# JTAG.net
KiCad netlist of a schematic drawn in Altium Designer
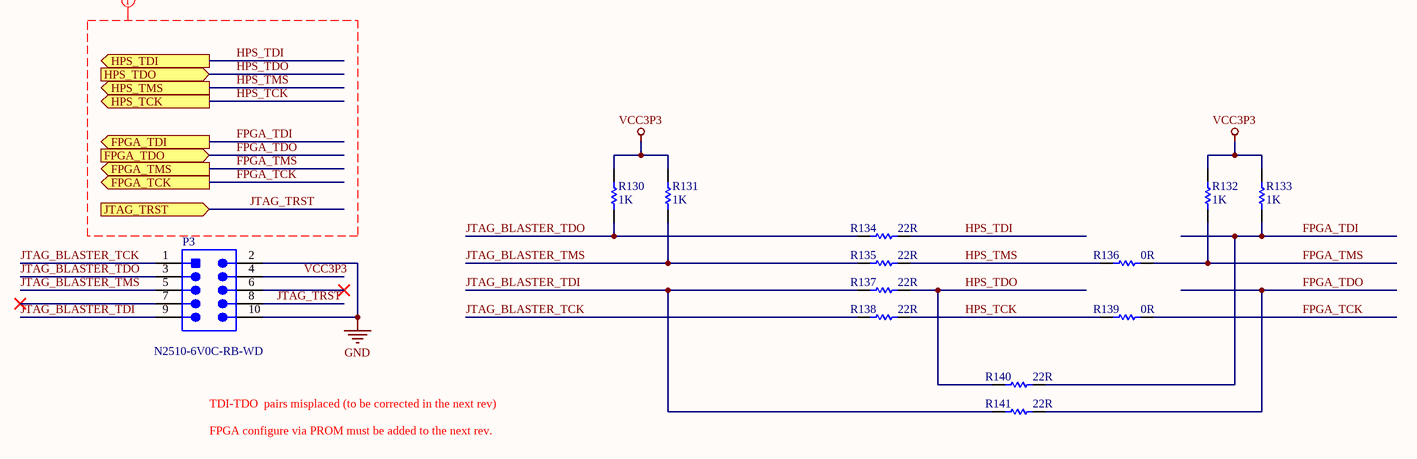
[diagram p0: JTAG.SchDoc]

(export (version "E")
  (design (tool "Eeschema 10.0.6"))
  (components
    (comp (ref "P3")
      (value "N2510-6V0C-RB-WD")
      (footprint "3M_N2510-6V0C-RB-WD")
      (description "Header, High Temperature, PCB Plug, 10 Cont, Solder Tail, Thru-Hole, 2500 Series, 2A")
      (fields (field (name "MANUFACTURER") "3M") (field (name "SOURCE") "ICNS_PropheseeLib.SchLib"))
      (libsource (lib "") (part "Symbol_1"))
    )
    (comp (ref "R130")
      (value "1K")
      (footprint "RES 0201 (0603)")
      (description "Res Thick Film 0201 1K Ohm 1% 0.05W(1/20W) ±200ppm/C Pad SMD Automotive T/R")
      (fields
        (field (name "TOLERANCE") "1%")
        (field (name "MANUFACTURER") "Yageo")
        (field (name "SOURCE") "ICNS_PropheseeLib.SchLib")
      )
      (libsource (lib "Western Sydney University - ICNS") (part "Symbol"))
    )
    (comp (ref "R131")
      (value "1K")
      (footprint "RES 0201 (0603)")
      (description "Res Thick Film 0201 1K Ohm 1% 0.05W(1/20W) ±200ppm/C Pad SMD Automotive T/R")
      (fields
        (field (name "TOLERANCE") "1%")
        (field (name "MANUFACTURER") "Yageo")
        (field (name "SOURCE") "ICNS_PropheseeLib.SchLib")
      )
      (libsource (lib "Western Sydney University - ICNS") (part "Symbol"))
    )
    (comp (ref "R132")
      (value "1K")
      (footprint "RES 0201 (0603)")
      (description "Res Thick Film 0201 1K Ohm 1% 0.05W(1/20W) ±200ppm/C Pad SMD Automotive T/R")
      (fields
        (field (name "TOLERANCE") "1%")
        (field (name "MANUFACTURER") "Yageo")
        (field (name "SOURCE") "ICNS_PropheseeLib.SchLib")
      )
      (libsource (lib "Western Sydney University - ICNS") (part "Symbol"))
    )
    (comp (ref "R133")
      (value "1K")
      (footprint "RES 0201 (0603)")
      (description "Res Thick Film 0201 1K Ohm 1% 0.05W(1/20W) ±200ppm/C Pad SMD Automotive T/R")
      (fields
        (field (name "TOLERANCE") "1%")
        (field (name "MANUFACTURER") "Yageo")
        (field (name "SOURCE") "ICNS_PropheseeLib.SchLib")
      )
      (libsource (lib "Western Sydney University - ICNS") (part "Symbol"))
    )
    (comp (ref "R134")
      (value "22R")
      (footprint "RES 0201 (0603)")
      (description "Res Thick Film 0201 22 Ohm 1% 0.05W(1/20W) ±200ppm/C Pad SMD Automotive T/R")
      (fields
        (field (name "TOLERANCE") "1%")
        (field (name "MANUFACTURER") "Yageo")
        (field (name "SOURCE") "ICNS_PropheseeLib.SchLib")
      )
      (libsource (lib "Western Sydney University - ICNS") (part "Symbol"))
    )
    (comp (ref "R135")
      (value "22R")
      (footprint "RES 0201 (0603)")
      (description "Res Thick Film 0201 22 Ohm 1% 0.05W(1/20W) ±200ppm/C Pad SMD Automotive T/R")
      (fields
        (field (name "TOLERANCE") "1%")
        (field (name "MANUFACTURER") "Yageo")
        (field (name "SOURCE") "ICNS_PropheseeLib.SchLib")
      )
      (libsource (lib "Western Sydney University - ICNS") (part "Symbol"))
    )
    (comp (ref "R136")
      (value "0R")
      (footprint "RES 0201 (0603)")
      (description "Res Thick Film 0201 0 Ohm Sulfur Resistant Pad SMD Automotive T/R")
      (fields
        (field (name "MANUFACTURER") "Yageo")
        (field (name "MANUFACTURER PART NUMBER") "AF0201JR-070RL")
        (field (name "SOURCE") "ICNS_PropheseeLib.SchLib")
      )
      (libsource (lib "Western Sydney University - ICNS") (part "Symbol"))
    )
    (comp (ref "R137")
      (value "22R")
      (footprint "RES 0201 (0603)")
      (description "Res Thick Film 0201 22 Ohm 1% 0.05W(1/20W) ±200ppm/C Pad SMD Automotive T/R")
      (fields
        (field (name "TOLERANCE") "1%")
        (field (name "MANUFACTURER") "Yageo")
        (field (name "SOURCE") "ICNS_PropheseeLib.SchLib")
      )
      (libsource (lib "Western Sydney University - ICNS") (part "Symbol"))
    )
    (comp (ref "R138")
      (value "22R")
      (footprint "RES 0201 (0603)")
      (description "Res Thick Film 0201 22 Ohm 1% 0.05W(1/20W) ±200ppm/C Pad SMD Automotive T/R")
      (fields
        (field (name "TOLERANCE") "1%")
        (field (name "MANUFACTURER") "Yageo")
        (field (name "SOURCE") "ICNS_PropheseeLib.SchLib")
      )
      (libsource (lib "Western Sydney University - ICNS") (part "Symbol"))
    )
    (comp (ref "R139")
      (value "0R")
      (footprint "RES 0201 (0603)")
      (description "Res Thick Film 0201 0 Ohm Sulfur Resistant Pad SMD Automotive T/R")
      (fields
        (field (name "MANUFACTURER") "Yageo")
        (field (name "MANUFACTURER PART NUMBER") "AF0201JR-070RL")
        (field (name "SOURCE") "ICNS_PropheseeLib.SchLib")
      )
      (libsource (lib "Western Sydney University - ICNS") (part "Symbol"))
    )
    (comp (ref "R140")
      (value "22R")
      (footprint "RES 0201 (0603)")
      (description "Res Thick Film 0201 22 Ohm 1% 0.05W(1/20W) ±200ppm/C Pad SMD Automotive T/R")
      (fields
        (field (name "TOLERANCE") "1%")
        (field (name "MANUFACTURER") "Yageo")
        (field (name "SOURCE") "ICNS_PropheseeLib.SchLib")
      )
      (libsource (lib "Western Sydney University - ICNS") (part "Symbol"))
    )
    (comp (ref "R141")
      (value "22R")
      (footprint "RES 0201 (0603)")
      (description "Res Thick Film 0201 22 Ohm 1% 0.05W(1/20W) ±200ppm/C Pad SMD Automotive T/R")
      (fields
        (field (name "TOLERANCE") "1%")
        (field (name "MANUFACTURER") "Yageo")
        (field (name "SOURCE") "ICNS_PropheseeLib.SchLib")
      )
      (libsource (lib "Western Sydney University - ICNS") (part "Symbol"))
    )
  )
  (nets
    (net (code "1") (name "/FPGA_TCK") (class "Default")
      (node (ref "R139") (pin "2") (pinfunction "2_2") (pintype "passive"))
    )
    (net (code "2") (name "/FPGA_TDI") (class "Default")
      (node (ref "R133") (pin "2") (pinfunction "2_2") (pintype "passive"))
      (node (ref "R140") (pin "2") (pinfunction "2_2") (pintype "passive"))
    )
    (net (code "3") (name "/FPGA_TDO") (class "Default")
      (node (ref "R141") (pin "2") (pinfunction "2_2") (pintype "passive"))
    )
    (net (code "4") (name "/FPGA_TMS") (class "Default")
      (node (ref "R132") (pin "2") (pinfunction "2_2") (pintype "passive"))
      (node (ref "R136") (pin "2") (pinfunction "2_2") (pintype "passive"))
    )
    (net (code "5") (name "/HPS_TCK") (class "Default")
      (node (ref "R138") (pin "2") (pinfunction "2_2") (pintype "passive"))
      (node (ref "R139") (pin "1") (pinfunction "1_1") (pintype "passive"))
    )
    (net (code "6") (name "/HPS_TDI") (class "Default")
      (node (ref "R134") (pin "2") (pinfunction "2_2") (pintype "passive"))
    )
    (net (code "7") (name "/HPS_TDO") (class "Default")
      (node (ref "R137") (pin "2") (pinfunction "2_2") (pintype "passive"))
      (node (ref "R140") (pin "1") (pinfunction "1_1") (pintype "passive"))
    )
    (net (code "8") (name "/HPS_TMS") (class "Default")
      (node (ref "R135") (pin "2") (pinfunction "2_2") (pintype "passive"))
      (node (ref "R136") (pin "1") (pinfunction "1_1") (pintype "passive"))
    )
    (net (code "9") (name "/JTAG_BLASTER_TCK") (class "Default")
      (node (ref "P3") (pin "1") (pinfunction "1_1") (pintype "passive"))
      (node (ref "R138") (pin "1") (pinfunction "1_1") (pintype "passive"))
    )
    (net (code "10") (name "/JTAG_BLASTER_TDI") (class "Default")
      (node (ref "P3") (pin "9") (pinfunction "9_9") (pintype "passive"))
      (node (ref "R137") (pin "1") (pinfunction "1_1") (pintype "passive"))
      (node (ref "R141") (pin "1") (pinfunction "1_1") (pintype "passive"))
    )
    (net (code "11") (name "/JTAG_BLASTER_TDO") (class "Default")
      (node (ref "P3") (pin "3") (pinfunction "3_3") (pintype "passive"))
      (node (ref "R130") (pin "2") (pinfunction "2_2") (pintype "passive"))
      (node (ref "R134") (pin "1") (pinfunction "1_1") (pintype "passive"))
    )
    (net (code "12") (name "/JTAG_BLASTER_TMS") (class "Default")
      (node (ref "P3") (pin "5") (pinfunction "5_5") (pintype "passive"))
      (node (ref "R131") (pin "2") (pinfunction "2_2") (pintype "passive"))
      (node (ref "R135") (pin "1") (pinfunction "1_1") (pintype "passive"))
    )
    (net (code "13") (name "/JTAG_TRST") (class "Default")
      (node (ref "P3") (pin "8") (pinfunction "8_8") (pintype "passive"))
    )
    (net (code "14") (name "GND") (class "Default")
      (node (ref "P3") (pin "10") (pinfunction "10_10") (pintype "passive"))
      (node (ref "P3") (pin "2") (pinfunction "2_2") (pintype "passive"))
    )
    (net (code "15") (name "VCC3P3") (class "Default")
      (node (ref "P3") (pin "4") (pinfunction "4_4") (pintype "passive"))
      (node (ref "R130") (pin "1") (pinfunction "1_1") (pintype "passive"))
      (node (ref "R131") (pin "1") (pinfunction "1_1") (pintype "passive"))
      (node (ref "R132") (pin "1") (pinfunction "1_1") (pintype "passive"))
      (node (ref "R133") (pin "1") (pinfunction "1_1") (pintype "passive"))
    )
    (net (code "16") (name "unconnected-(P3-Pad6)") (class "Default")
      (node (ref "P3") (pin "6") (pinfunction "6_6") (pintype "passive+no_connect"))
    )
    (net (code "17") (name "unconnected-(P3-Pad7)") (class "Default")
      (node (ref "P3") (pin "7") (pinfunction "7_7") (pintype "passive+no_connect"))
    )
  )
)
